# CiderPress.net
KiCad netlist of a schematic drawn in EAGLE
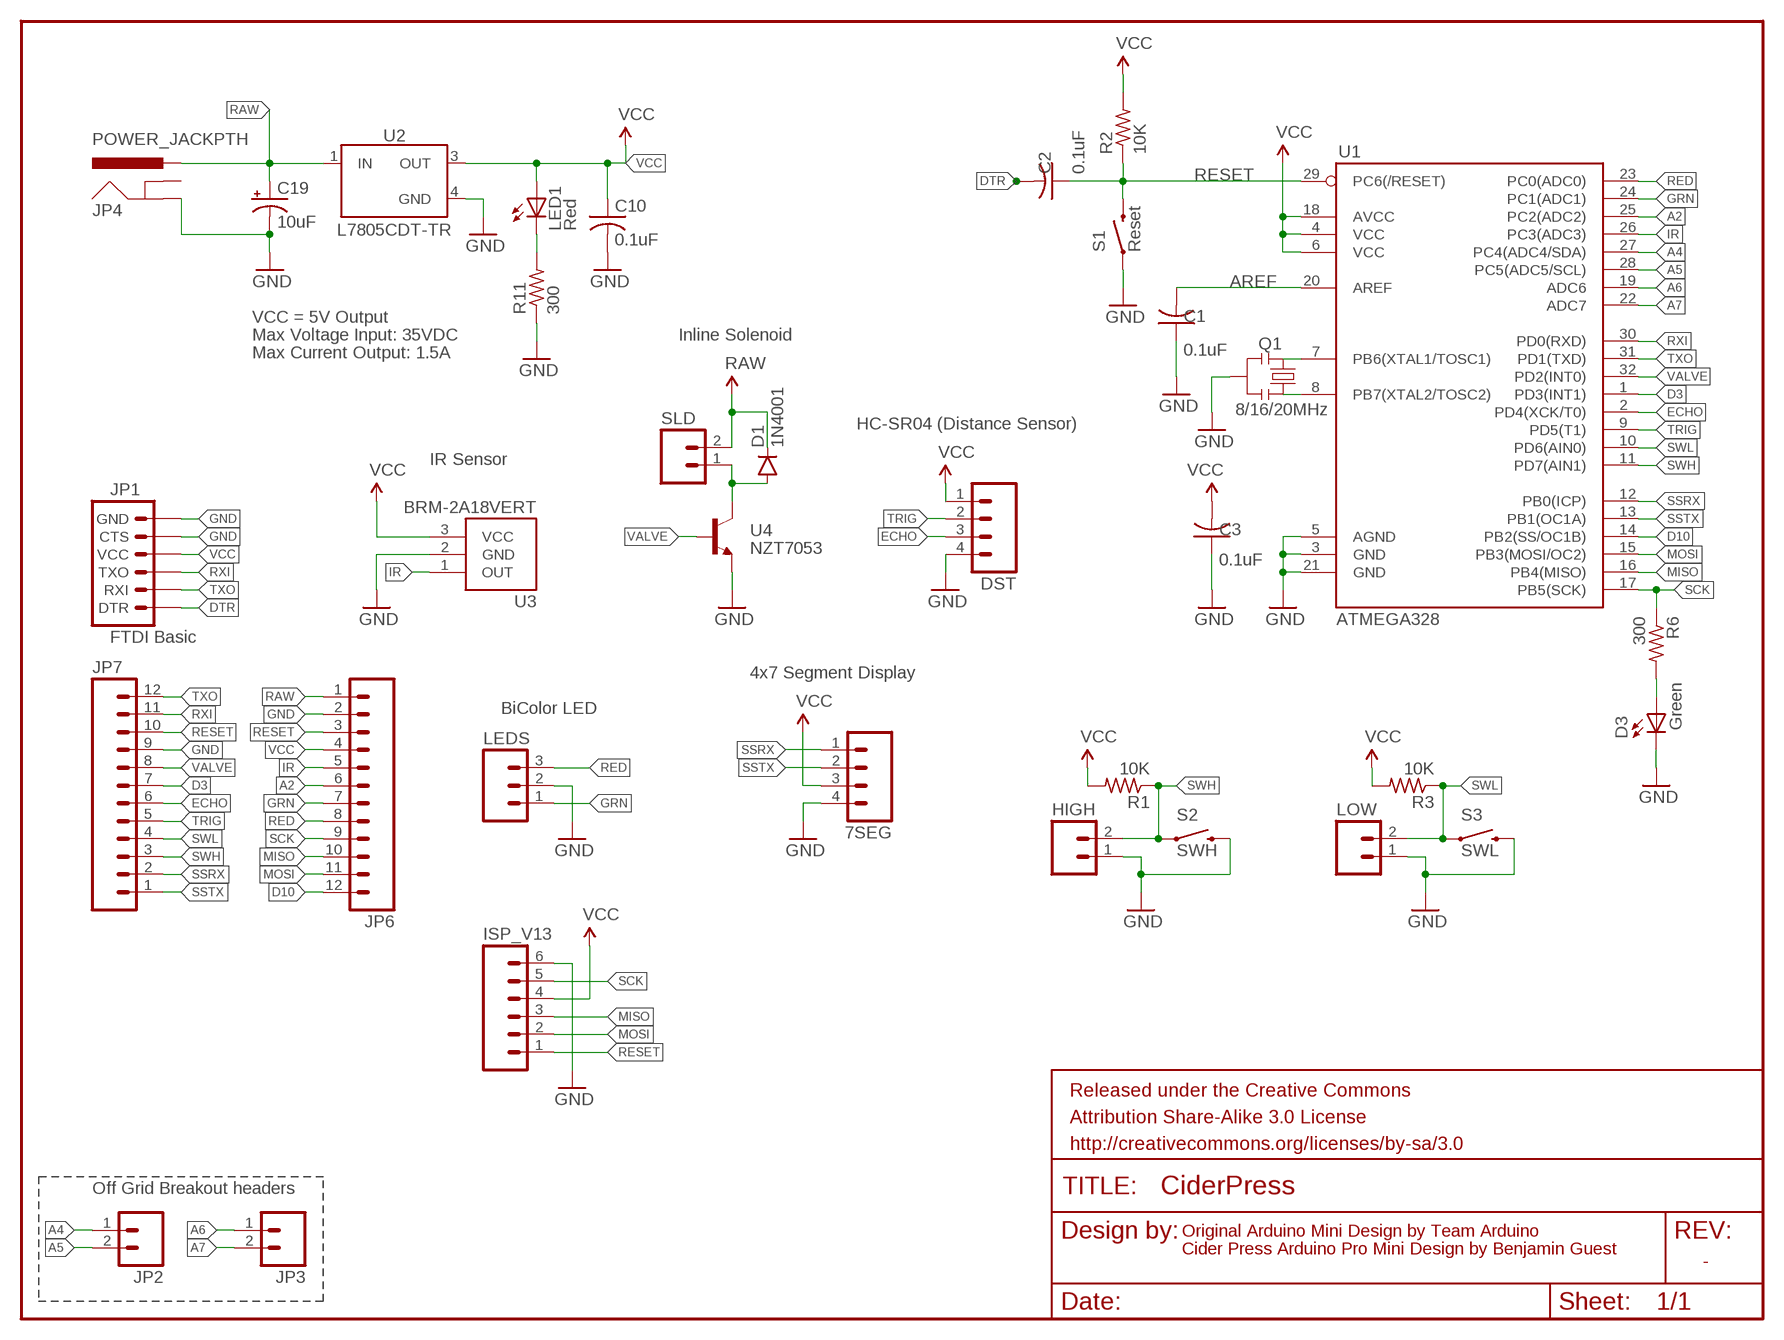
[diagram p0: schematic, sheet 1]

(export (version "E")
  (design (tool "Eeschema 10.0.6"))
  (components
    (comp (ref "7SEG")
      (value "M04JST-PTH")
      (footprint "eagle-import:JST-4-PTH")
      (libsource (lib "eagle-import") (part "M04JST-PTH"))
    )
    (comp (ref "C1")
      (value "0.1uF")
      (footprint "eagle-import:C0805")
      (libsource (lib "eagle-import") (part "C-USC0805"))
    )
    (comp (ref "C2")
      (value "0.1uF")
      (footprint "eagle-import:C0805")
      (libsource (lib "eagle-import") (part "C-USC0805"))
    )
    (comp (ref "C3")
      (value "0.1uF")
      (footprint "eagle-import:C0805")
      (libsource (lib "eagle-import") (part "C-USC0805"))
    )
    (comp (ref "C10")
      (value "0.1uF")
      (footprint "eagle-import:C0805")
      (libsource (lib "eagle-import") (part "C-USC0805"))
    )
    (comp (ref "C19")
      (value "10uF")
      (footprint "eagle-import:EIA3216")
      (libsource (lib "eagle-import") (part "CAP_POL1206"))
    )
    (comp (ref "D1")
      (value "1N4001")
      (footprint "eagle-import:DIODE-1N4001-KIT")
      (libsource (lib "eagle-import") (part "DIODEKIT2"))
    )
    (comp (ref "D3")
      (value "Green")
      (footprint "eagle-import:CHIPLED_0805")
      (libsource (lib "eagle-import") (part "LEDCHIPLED_0805"))
    )
    (comp (ref "DST")
      (value "M04JST-PTH")
      (footprint "eagle-import:JST-4-PTH")
      (libsource (lib "eagle-import") (part "M04JST-PTH"))
    )
    (comp (ref "FRAME1")
      (value "FRAME-LETTER")
      (footprint "eagle-import:CREATIVE_COMMONS")
      (libsource (lib "eagle-import") (part "FRAME-LETTER"))
    )
    (comp (ref "HIGH")
      (value "M02JST-PTH-2")
      (footprint "eagle-import:JST-2-PTH")
      (libsource (lib "eagle-import") (part "SparkFun-Connectors_M02JST-PTH-2"))
    )
    (comp (ref "ISP_V13")
      (value "M06SIP")
      (footprint "eagle-import:1X06")
      (libsource (lib "eagle-import") (part "M06SIP"))
    )
    (comp (ref "JP1")
      (value "FTDI Basic")
      (footprint "eagle-import:1X06")
      (libsource (lib "eagle-import") (part "ARDUINO_SERIAL_PROGRAMPTH"))
    )
    (comp (ref "JP2")
      (value "M02PTH")
      (footprint "eagle-import:1X02")
      (libsource (lib "eagle-import") (part "M02PTH"))
    )
    (comp (ref "JP3")
      (value "M02PTH")
      (footprint "eagle-import:1X02")
      (libsource (lib "eagle-import") (part "M02PTH"))
    )
    (comp (ref "JP4")
      (value "POWER_JACKPTH")
      (footprint "eagle-import:POWER_JACK_PTH")
      (libsource (lib "eagle-import") (part "POWER_JACKPTH"))
    )
    (comp (ref "JP6")
      (value "M12PTH")
      (footprint "eagle-import:1X12")
      (libsource (lib "eagle-import") (part "M12PTH"))
    )
    (comp (ref "JP7")
      (value "M12PTH")
      (footprint "eagle-import:1X12")
      (libsource (lib "eagle-import") (part "M12PTH"))
    )
    (comp (ref "LED1")
      (value "Red")
      (footprint "eagle-import:CHIPLED_0805")
      (libsource (lib "eagle-import") (part "LEDCHIPLED_0805"))
    )
    (comp (ref "LEDS")
      (value "M03JST-PTH")
      (footprint "eagle-import:JST-3-PTH")
      (libsource (lib "eagle-import") (part "M03JST-PTH"))
    )
    (comp (ref "LOW")
      (value "M02JST-PTH-2")
      (footprint "eagle-import:JST-2-PTH")
      (libsource (lib "eagle-import") (part "SparkFun-Connectors_M02JST-PTH-2"))
    )
    (comp (ref "Q1")
      (value "8/16/20MHz")
      (footprint "eagle-import:RESONATOR-SMD-1_1")
      (libsource (lib "eagle-import") (part "RESONATOR1{colon}1"))
    )
    (comp (ref "R1")
      (value "10K")
      (footprint "eagle-import:M0805")
      (libsource (lib "eagle-import") (part "R-US_M0805"))
    )
    (comp (ref "R2")
      (value "10K")
      (footprint "eagle-import:M0805")
      (libsource (lib "eagle-import") (part "R-US_M0805"))
    )
    (comp (ref "R3")
      (value "10K")
      (footprint "eagle-import:M0805")
      (libsource (lib "eagle-import") (part "R-US_M0805"))
    )
    (comp (ref "R6")
      (value "300")
      (footprint "eagle-import:M0805")
      (libsource (lib "eagle-import") (part "R-US_M0805"))
    )
    (comp (ref "R11")
      (value "300")
      (footprint "eagle-import:M0805")
      (libsource (lib "eagle-import") (part "R-US_M0805"))
    )
    (comp (ref "S1")
      (value "Reset")
      (footprint "eagle-import:TACTILE-SWITCH-SMD-ALT01")
      (libsource (lib "eagle-import") (part "SWITCH-MOMENTARY-2SMD-ALT01"))
    )
    (comp (ref "S2")
      (value "SWH")
      (footprint "eagle-import:TACTILE-SWITCH-SMD-ALT01")
      (libsource (lib "eagle-import") (part "SWITCH-MOMENTARY-2SMD-ALT01"))
    )
    (comp (ref "S3")
      (value "SWL")
      (footprint "eagle-import:TACTILE-SWITCH-SMD-ALT01")
      (libsource (lib "eagle-import") (part "SWITCH-MOMENTARY-2SMD-ALT01"))
    )
    (comp (ref "SLD")
      (value "M02JST-PTH-2")
      (footprint "eagle-import:JST-2-PTH")
      (libsource (lib "eagle-import") (part "SparkFun-Connectors_M02JST-PTH-2"))
    )
    (comp (ref "U1")
      (value "ATMEGA328")
      (footprint "eagle-import:TQFP32-08")
      (libsource (lib "eagle-import") (part "ATMEGA168"))
    )
    (comp (ref "U2")
      (value "L7805CDT-TR")
      (footprint "eagle-import:DPAK")
      (libsource (lib "eagle-import") (part "L7805CDT-TR"))
    )
    (comp (ref "U3")
      (value "BRM-2A18VERT")
      (footprint "eagle-import:BRM-2508_VERT")
      (libsource (lib "eagle-import") (part "BRM-2A18VERT"))
    )
    (comp (ref "U4")
      (value "NZT7053")
      (footprint "eagle-import:SOT-223")
      (libsource (lib "eagle-import") (part "NZT7053"))
    )
  )
  (nets
    (net (code "1") (name "/AREF") (class "Default")
      (node (ref "C1") (pin "2") (pinfunction "2_2") (pintype "passive"))
      (node (ref "U1") (pin "20") (pinfunction "AREF_20") (pintype "bidirectional"))
    )
    (net (code "2") (name "A2") (class "Default")
      (node (ref "JP6") (pin "6") (pinfunction "6_6") (pintype "passive"))
      (node (ref "U1") (pin "25") (pinfunction "PC2(ADC2)_25") (pintype "bidirectional"))
    )
    (net (code "3") (name "A4") (class "Default")
      (node (ref "JP2") (pin "1") (pinfunction "1_1") (pintype "passive"))
      (node (ref "U1") (pin "27") (pinfunction "PC4(ADC4/SDA)_27") (pintype "bidirectional"))
    )
    (net (code "4") (name "A5") (class "Default")
      (node (ref "JP2") (pin "2") (pinfunction "2_2") (pintype "passive"))
      (node (ref "U1") (pin "28") (pinfunction "PC5(ADC5/SCL)_28") (pintype "bidirectional"))
    )
    (net (code "5") (name "A6") (class "Default")
      (node (ref "JP3") (pin "1") (pinfunction "1_1") (pintype "passive"))
      (node (ref "U1") (pin "19") (pinfunction "ADC6_19") (pintype "bidirectional"))
    )
    (net (code "6") (name "A7") (class "Default")
      (node (ref "JP3") (pin "2") (pinfunction "2_2") (pintype "passive"))
      (node (ref "U1") (pin "22") (pinfunction "ADC7_22") (pintype "bidirectional"))
    )
    (net (code "7") (name "D3") (class "Default")
      (node (ref "JP7") (pin "7") (pinfunction "7_7") (pintype "passive"))
      (node (ref "U1") (pin "1") (pinfunction "PD3(INT1)_1") (pintype "bidirectional"))
    )
    (net (code "8") (name "D10") (class "Default")
      (node (ref "JP6") (pin "12") (pinfunction "12_12") (pintype "passive"))
      (node (ref "U1") (pin "14") (pinfunction "PB2(SS/OC1B)_14") (pintype "bidirectional"))
    )
    (net (code "9") (name "DTR") (class "Default")
      (node (ref "C2") (pin "2") (pinfunction "2_2") (pintype "passive"))
      (node (ref "JP1") (pin "1") (pinfunction "DTR_1") (pintype "passive"))
    )
    (net (code "10") (name "ECHO") (class "Default")
      (node (ref "DST") (pin "3") (pinfunction "3_3") (pintype "passive"))
      (node (ref "JP7") (pin "6") (pinfunction "6_6") (pintype "passive"))
      (node (ref "U1") (pin "2") (pinfunction "PD4(XCK/T0)_2") (pintype "bidirectional"))
    )
    (net (code "11") (name "GND") (class "Default")
      (node (ref "7SEG") (pin "4") (pinfunction "4_4") (pintype "passive"))
      (node (ref "C1") (pin "1") (pinfunction "1_1") (pintype "passive"))
      (node (ref "C10") (pin "2") (pinfunction "2_2") (pintype "passive"))
      (node (ref "C19") (pin "C") (pinfunction "-_C") (pintype "passive"))
      (node (ref "C3") (pin "1") (pinfunction "1_1") (pintype "passive"))
      (node (ref "D3") (pin "C") (pinfunction "C_C") (pintype "passive"))
      (node (ref "DST") (pin "4") (pinfunction "4_4") (pintype "passive"))
      (node (ref "HIGH") (pin "1") (pinfunction "1_1") (pintype "passive"))
      (node (ref "ISP_V13") (pin "6") (pinfunction "6_6") (pintype "passive"))
      (node (ref "JP1") (pin "5") (pinfunction "CTS_5") (pintype "passive"))
      (node (ref "JP1") (pin "6") (pinfunction "GND_6") (pintype "passive"))
      (node (ref "JP4") (pin "GND") (pinfunction "GND_GND") (pintype "bidirectional"))
      (node (ref "JP6") (pin "2") (pinfunction "2_2") (pintype "passive"))
      (node (ref "JP7") (pin "9") (pinfunction "9_9") (pintype "passive"))
      (node (ref "LEDS") (pin "2") (pinfunction "2_2") (pintype "passive"))
      (node (ref "LOW") (pin "1") (pinfunction "1_1") (pintype "passive"))
      (node (ref "Q1") (pin "2") (pinfunction "2_2") (pintype "passive"))
      (node (ref "R11") (pin "1") (pinfunction "1_1") (pintype "passive"))
      (node (ref "S1") (pin "1") (pinfunction "1_1") (pintype "passive"))
      (node (ref "S1") (pin "2") (pinfunction "1_2") (pintype "passive"))
      (node (ref "S2") (pin "3") (pinfunction "2_3") (pintype "passive"))
      (node (ref "S2") (pin "4") (pinfunction "2_4") (pintype "passive"))
      (node (ref "S3") (pin "3") (pinfunction "2_3") (pintype "passive"))
      (node (ref "S3") (pin "4") (pinfunction "2_4") (pintype "passive"))
      (node (ref "U1") (pin "21") (pinfunction "GND_21") (pintype "bidirectional"))
      (node (ref "U1") (pin "3") (pinfunction "GND_3") (pintype "bidirectional"))
      (node (ref "U1") (pin "5") (pinfunction "AGND_5") (pintype "bidirectional"))
      (node (ref "U2") (pin "4") (pinfunction "GND_4") (pintype "power_in"))
      (node (ref "U3") (pin "2") (pinfunction "GND_2") (pintype "bidirectional"))
      (node (ref "U4") (pin "3") (pinfunction "E_3") (pintype "passive"))
    )
    (net (code "12") (name "GRN") (class "Default")
      (node (ref "JP6") (pin "7") (pinfunction "7_7") (pintype "passive"))
      (node (ref "LEDS") (pin "1") (pinfunction "1_1") (pintype "passive"))
      (node (ref "U1") (pin "24") (pinfunction "PC1(ADC1)_24") (pintype "bidirectional"))
    )
    (net (code "13") (name "IR") (class "Default")
      (node (ref "JP6") (pin "5") (pinfunction "5_5") (pintype "passive"))
      (node (ref "U1") (pin "26") (pinfunction "PC3(ADC3)_26") (pintype "bidirectional"))
      (node (ref "U3") (pin "1") (pinfunction "OUT_1") (pintype "bidirectional"))
    )
    (net (code "14") (name "MISO") (class "Default")
      (node (ref "ISP_V13") (pin "3") (pinfunction "3_3") (pintype "passive"))
      (node (ref "JP6") (pin "10") (pinfunction "10_10") (pintype "passive"))
      (node (ref "U1") (pin "16") (pinfunction "PB4(MISO)_16") (pintype "bidirectional"))
    )
    (net (code "15") (name "MOSI") (class "Default")
      (node (ref "ISP_V13") (pin "2") (pinfunction "2_2") (pintype "passive"))
      (node (ref "JP6") (pin "11") (pinfunction "11_11") (pintype "passive"))
      (node (ref "U1") (pin "15") (pinfunction "PB3(MOSI/OC2)_15") (pintype "bidirectional"))
    )
    (net (code "16") (name "Net-(D1-PadA)") (class "Default")
      (node (ref "D1") (pin "A") (pinfunction "A_A") (pintype "passive"))
      (node (ref "SLD") (pin "1") (pinfunction "1_1") (pintype "passive"))
      (node (ref "U4") (pin "2") (pinfunction "C_2") (pintype "passive"))
      (node (ref "U4") (pin "4") (pinfunction "C_4") (pintype "passive"))
    )
    (net (code "17") (name "Net-(D3-PadA)") (class "Default")
      (node (ref "D3") (pin "A") (pinfunction "A_A") (pintype "passive"))
      (node (ref "R6") (pin "2") (pinfunction "2_2") (pintype "passive"))
    )
    (net (code "18") (name "Net-(LED1-PadC)") (class "Default")
      (node (ref "LED1") (pin "C") (pinfunction "C_C") (pintype "passive"))
      (node (ref "R11") (pin "2") (pinfunction "2_2") (pintype "passive"))
    )
    (net (code "19") (name "Net-(U1-PB6(XTAL1{slash}TOSC1))") (class "Default")
      (node (ref "Q1") (pin "1") (pinfunction "1_1") (pintype "passive"))
      (node (ref "U1") (pin "7") (pinfunction "PB6(XTAL1/TOSC1)_7") (pintype "bidirectional"))
    )
    (net (code "20") (name "Net-(U1-PB7(XTAL2{slash}TOSC2))") (class "Default")
      (node (ref "Q1") (pin "3") (pinfunction "3_3") (pintype "passive"))
      (node (ref "U1") (pin "8") (pinfunction "PB7(XTAL2/TOSC2)_8") (pintype "bidirectional"))
    )
    (net (code "21") (name "RAW") (class "Default")
      (node (ref "C19") (pin "A") (pinfunction "+_A") (pintype "passive"))
      (node (ref "D1") (pin "C") (pinfunction "C_C") (pintype "passive"))
      (node (ref "JP4") (pin "PWR") (pinfunction "PWR_PWR") (pintype "bidirectional"))
      (node (ref "JP6") (pin "1") (pinfunction "1_1") (pintype "passive"))
      (node (ref "SLD") (pin "2") (pinfunction "2_2") (pintype "passive"))
      (node (ref "U2") (pin "1") (pinfunction "IN_1") (pintype "power_in"))
    )
    (net (code "22") (name "RED") (class "Default")
      (node (ref "JP6") (pin "8") (pinfunction "8_8") (pintype "passive"))
      (node (ref "LEDS") (pin "3") (pinfunction "3_3") (pintype "passive"))
      (node (ref "U1") (pin "23") (pinfunction "PC0(ADC0)_23") (pintype "bidirectional"))
    )
    (net (code "23") (name "RESET") (class "Default")
      (node (ref "C2") (pin "1") (pinfunction "1_1") (pintype "passive"))
      (node (ref "ISP_V13") (pin "1") (pinfunction "1_1") (pintype "passive"))
      (node (ref "JP6") (pin "3") (pinfunction "3_3") (pintype "passive"))
      (node (ref "JP7") (pin "10") (pinfunction "10_10") (pintype "passive"))
      (node (ref "R2") (pin "1") (pinfunction "1_1") (pintype "passive"))
      (node (ref "S1") (pin "3") (pinfunction "2_3") (pintype "passive"))
      (node (ref "S1") (pin "4") (pinfunction "2_4") (pintype "passive"))
      (node (ref "U1") (pin "29") (pinfunction "PC6(/RESET)_29") (pintype "bidirectional"))
    )
    (net (code "24") (name "RXI") (class "Default")
      (node (ref "JP1") (pin "3") (pinfunction "TXO_3") (pintype "passive"))
      (node (ref "JP7") (pin "11") (pinfunction "11_11") (pintype "passive"))
      (node (ref "U1") (pin "30") (pinfunction "PD0(RXD)_30") (pintype "bidirectional"))
    )
    (net (code "25") (name "SCK") (class "Default")
      (node (ref "ISP_V13") (pin "5") (pinfunction "5_5") (pintype "passive"))
      (node (ref "JP6") (pin "9") (pinfunction "9_9") (pintype "passive"))
      (node (ref "R6") (pin "1") (pinfunction "1_1") (pintype "passive"))
      (node (ref "U1") (pin "17") (pinfunction "PB5(SCK)_17") (pintype "bidirectional"))
    )
    (net (code "26") (name "SSRX") (class "Default")
      (node (ref "7SEG") (pin "1") (pinfunction "1_1") (pintype "passive"))
      (node (ref "JP7") (pin "2") (pinfunction "2_2") (pintype "passive"))
      (node (ref "U1") (pin "12") (pinfunction "PB0(ICP)_12") (pintype "bidirectional"))
    )
    (net (code "27") (name "SSTX") (class "Default")
      (node (ref "7SEG") (pin "2") (pinfunction "2_2") (pintype "passive"))
      (node (ref "JP7") (pin "1") (pinfunction "1_1") (pintype "passive"))
      (node (ref "U1") (pin "13") (pinfunction "PB1(OC1A)_13") (pintype "bidirectional"))
    )
    (net (code "28") (name "SWH") (class "Default")
      (node (ref "HIGH") (pin "2") (pinfunction "2_2") (pintype "passive"))
      (node (ref "JP7") (pin "3") (pinfunction "3_3") (pintype "passive"))
      (node (ref "R1") (pin "1") (pinfunction "1_1") (pintype "passive"))
      (node (ref "S2") (pin "1") (pinfunction "1_1") (pintype "passive"))
      (node (ref "S2") (pin "2") (pinfunction "1_2") (pintype "passive"))
      (node (ref "U1") (pin "11") (pinfunction "PD7(AIN1)_11") (pintype "bidirectional"))
    )
    (net (code "29") (name "SWL") (class "Default")
      (node (ref "JP7") (pin "4") (pinfunction "4_4") (pintype "passive"))
      (node (ref "LOW") (pin "2") (pinfunction "2_2") (pintype "passive"))
      (node (ref "R3") (pin "1") (pinfunction "1_1") (pintype "passive"))
      (node (ref "S3") (pin "1") (pinfunction "1_1") (pintype "passive"))
      (node (ref "S3") (pin "2") (pinfunction "1_2") (pintype "passive"))
      (node (ref "U1") (pin "10") (pinfunction "PD6(AIN0)_10") (pintype "bidirectional"))
    )
    (net (code "30") (name "TRIG") (class "Default")
      (node (ref "DST") (pin "2") (pinfunction "2_2") (pintype "passive"))
      (node (ref "JP7") (pin "5") (pinfunction "5_5") (pintype "passive"))
      (node (ref "U1") (pin "9") (pinfunction "PD5(T1)_9") (pintype "bidirectional"))
    )
    (net (code "31") (name "TXO") (class "Default")
      (node (ref "JP1") (pin "2") (pinfunction "RXI_2") (pintype "passive"))
      (node (ref "JP7") (pin "12") (pinfunction "12_12") (pintype "passive"))
      (node (ref "U1") (pin "31") (pinfunction "PD1(TXD)_31") (pintype "bidirectional"))
    )
    (net (code "32") (name "VALVE") (class "Default")
      (node (ref "JP7") (pin "8") (pinfunction "8_8") (pintype "passive"))
      (node (ref "U1") (pin "32") (pinfunction "PD2(INT0)_32") (pintype "bidirectional"))
      (node (ref "U4") (pin "1") (pinfunction "B_1") (pintype "passive"))
    )
    (net (code "33") (name "VCC") (class "Default")
      (node (ref "7SEG") (pin "3") (pinfunction "3_3") (pintype "passive"))
      (node (ref "C10") (pin "1") (pinfunction "1_1") (pintype "passive"))
      (node (ref "C3") (pin "2") (pinfunction "2_2") (pintype "passive"))
      (node (ref "DST") (pin "1") (pinfunction "1_1") (pintype "passive"))
      (node (ref "ISP_V13") (pin "4") (pinfunction "4_4") (pintype "passive"))
      (node (ref "JP1") (pin "4") (pinfunction "VCC_4") (pintype "passive"))
      (node (ref "JP6") (pin "4") (pinfunction "4_4") (pintype "passive"))
      (node (ref "LED1") (pin "A") (pinfunction "A_A") (pintype "passive"))
      (node (ref "R1") (pin "2") (pinfunction "2_2") (pintype "passive"))
      (node (ref "R2") (pin "2") (pinfunction "2_2") (pintype "passive"))
      (node (ref "R3") (pin "2") (pinfunction "2_2") (pintype "passive"))
      (node (ref "U1") (pin "18") (pinfunction "AVCC_18") (pintype "bidirectional"))
      (node (ref "U1") (pin "4") (pinfunction "VCC_4") (pintype "bidirectional"))
      (node (ref "U1") (pin "6") (pinfunction "VCC_6") (pintype "bidirectional"))
      (node (ref "U2") (pin "3") (pinfunction "OUT_3") (pintype "power_in"))
      (node (ref "U3") (pin "3") (pinfunction "VCC_3") (pintype "bidirectional"))
    )
    (net (code "34") (name "unconnected-(JP4-PadGNDBREAK)") (class "Default")
      (node (ref "JP4") (pin "GNDBREAK") (pinfunction "GNDBREAK_GNDBREAK") (pintype "bidirectional"))
    )
  )
)
